# SCH_AC400-Controller_2024-06-21.net
KiCad netlist of a schematic drawn in EasyEDA
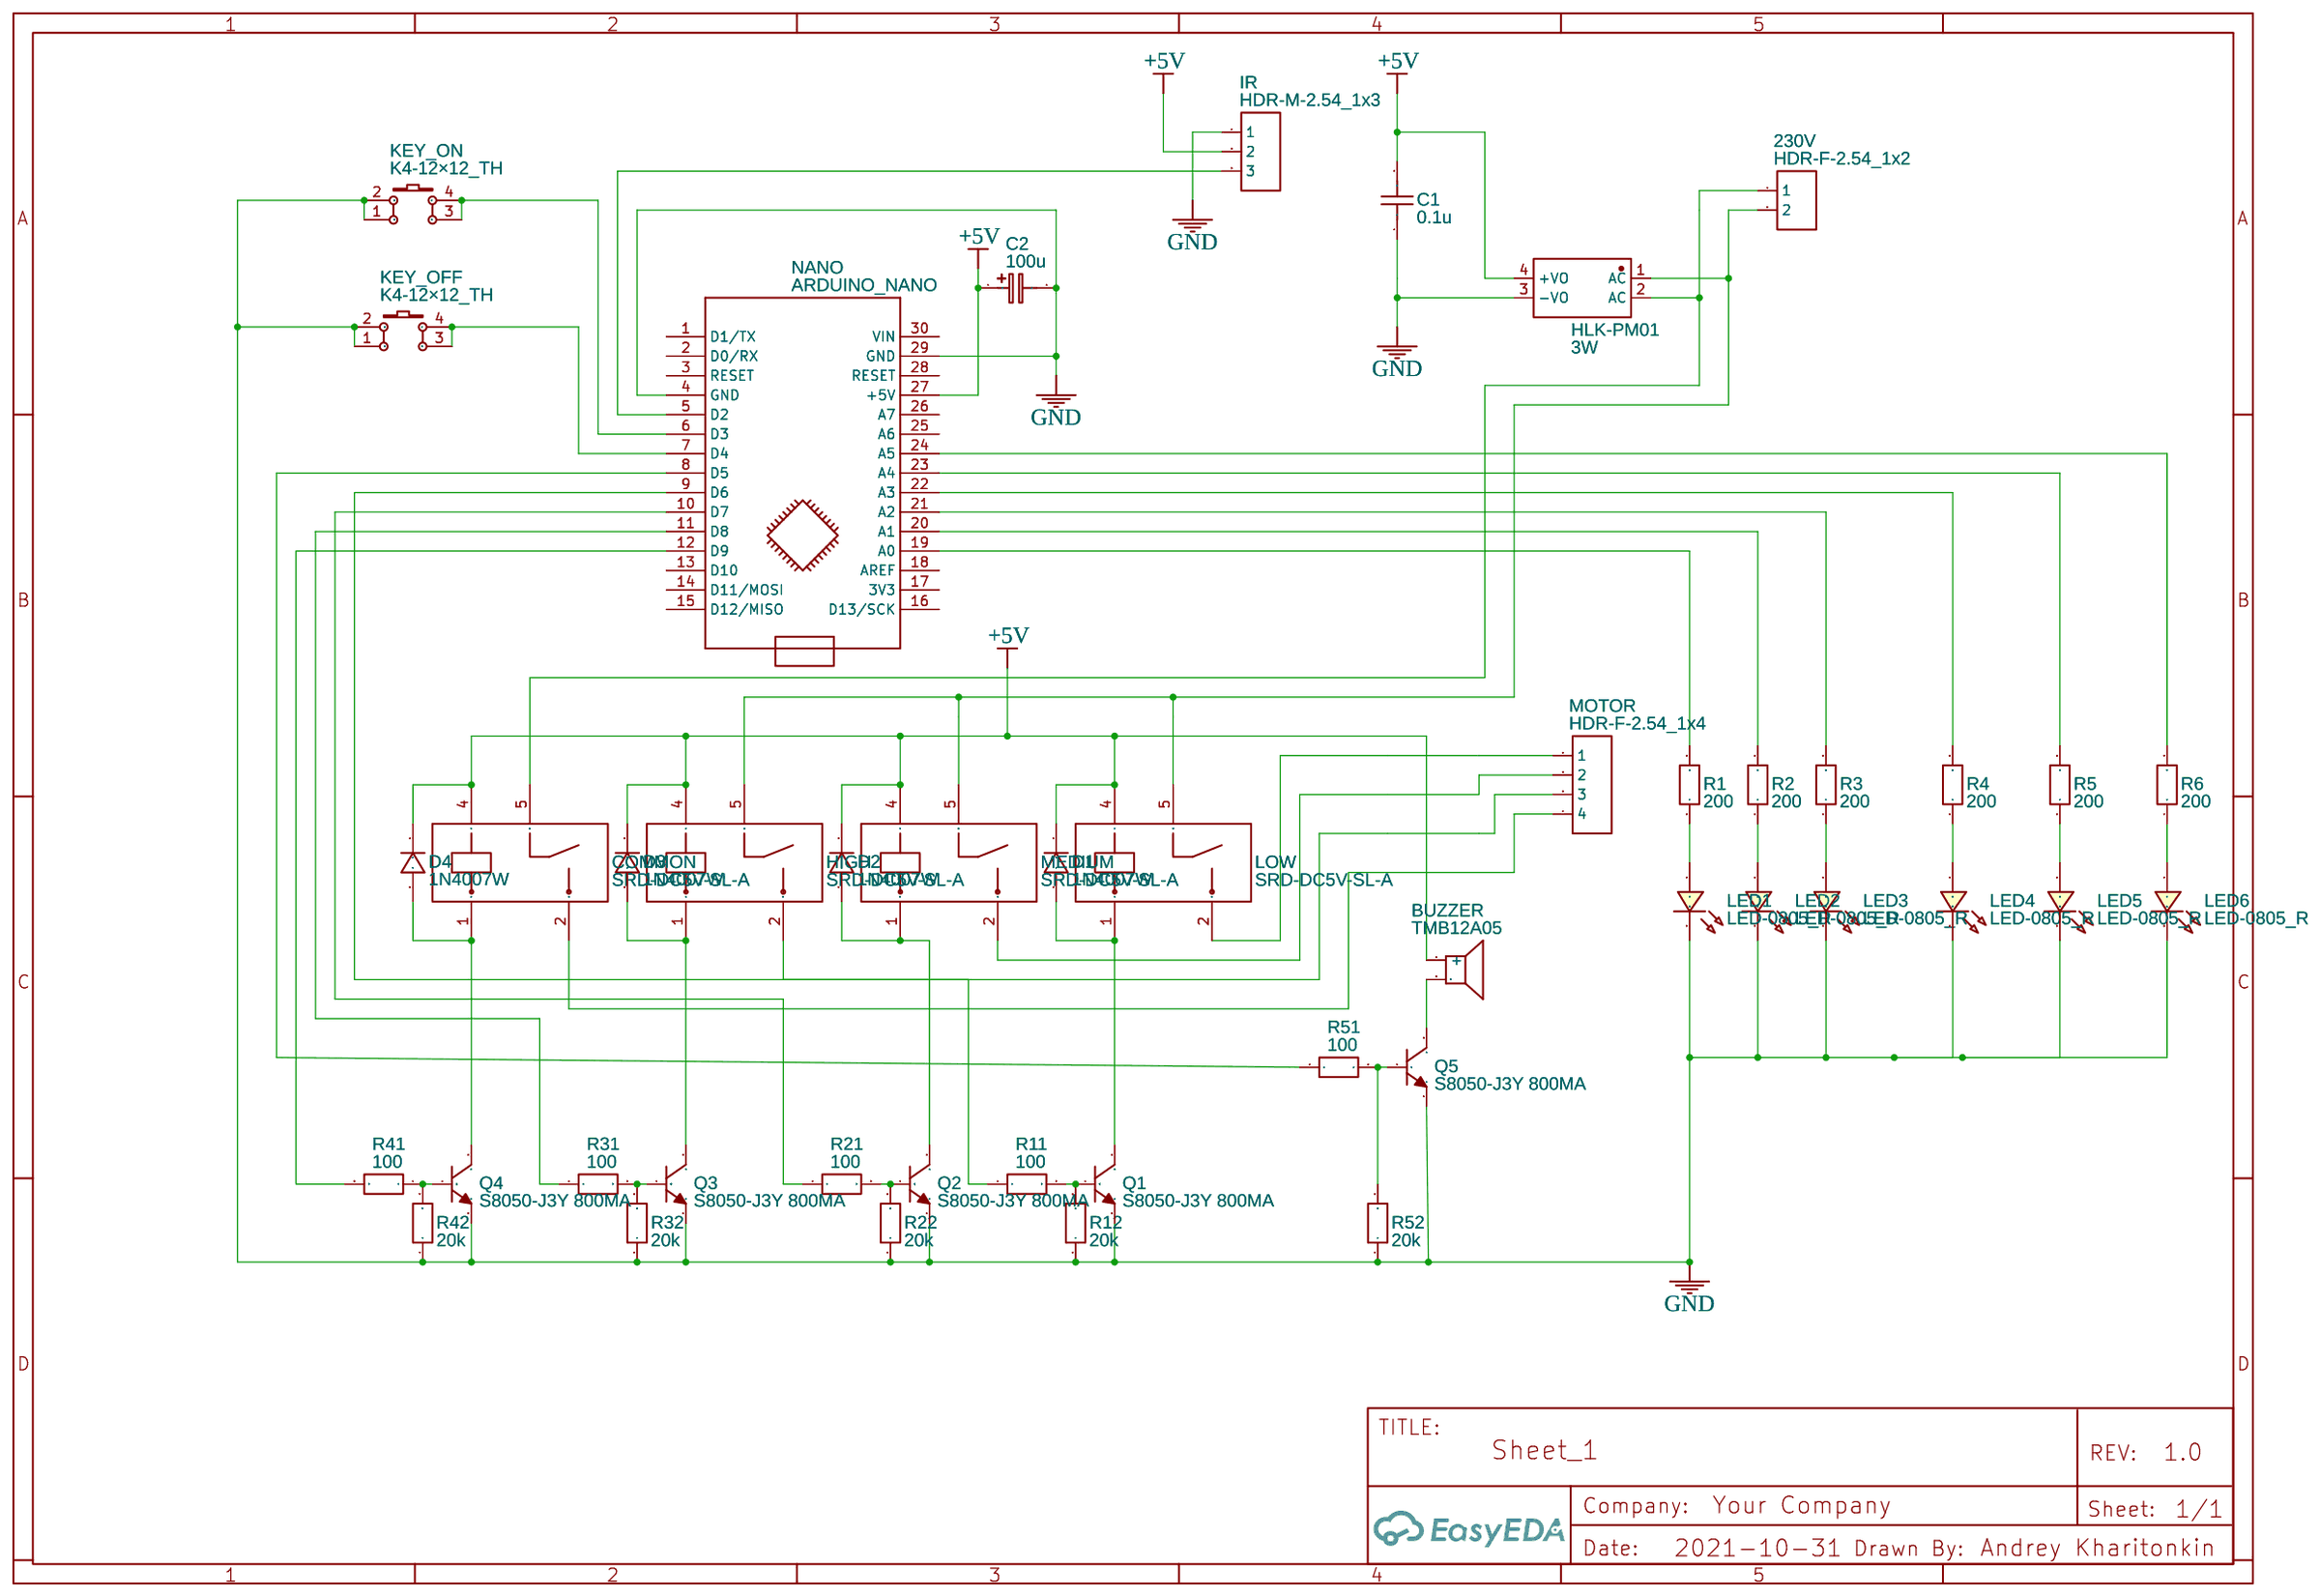
[diagram p0: schematic sheet]

(export (version "E")
  (design (tool "Eeschema 10.0.6"))
  (components
    (comp (ref "3W")
      (value "HLK-PM01")
      (fields (field (name "Manufacturer") "HI-LINK"))
      (libsource (lib "") (part "HLK-PM01"))
    )
    (comp (ref "230V") (value "HDR-F-2.54_1x2") (libsource (lib "") (part "HDR-F-2.54_1x2")))
    (comp (ref "BUZZER")
      (value "TMB12A05")
      (fields (field (name "Manufacturer") "HNDZ"))
      (libsource (lib "") (part "TMB12A05"))
    )
    (comp (ref "C1")
      (value "0.1u")
      (fields
        (field (name "Manufacturer Part") "CT41G-0805-2X1-50V-0.1uF-K(N)")
        (field (name "Manufacturer") "TORCH")
      )
      (libsource (lib "") (part "C_1206_US"))
    )
    (comp (ref "C2") (value "100u") (libsource (lib "") (part "CE_TH_D6.3×F2.5_EU")))
    (comp (ref "COMMON")
      (value "SRD-DC5V-SL-A")
      (fields (field (name "Manufacturer") "Ningbo Songle Relay"))
      (libsource (lib "") (part "SRD-DC5V-SL-A_2"))
    )
    (comp (ref "D1")
      (value "1N4007W")
      (fields (field (name "Manufacturer") "BLUE ROCKET"))
      (libsource (lib "") (part "1N4007W"))
    )
    (comp (ref "D2")
      (value "1N4007W")
      (fields (field (name "Manufacturer") "BLUE ROCKET"))
      (libsource (lib "") (part "1N4007W"))
    )
    (comp (ref "D3")
      (value "1N4007W")
      (fields (field (name "Manufacturer") "BLUE ROCKET"))
      (libsource (lib "") (part "1N4007W"))
    )
    (comp (ref "D4")
      (value "1N4007W")
      (fields (field (name "Manufacturer") "BLUE ROCKET"))
      (libsource (lib "") (part "1N4007W"))
    )
    (comp (ref "HIGH")
      (value "SRD-DC5V-SL-A")
      (fields (field (name "Manufacturer") "Ningbo Songle Relay"))
      (libsource (lib "") (part "SRD-DC5V-SL-A_1"))
    )
    (comp (ref "IR") (value "HDR-M-2.54_1x3") (libsource (lib "") (part "HDR-M-2.54_1x3")))
    (comp (ref "KEY_OFF")
      (value "K4-12×12_TH")
      (fields (field (name "Manufacturer Part") "K2-1103DP-M4SW-04") (field (name "Manufacturer") "韩国韩荣"))
      (libsource (lib "") (part "K4-12×12_TH_1"))
    )
    (comp (ref "KEY_ON")
      (value "K4-12×12_TH")
      (fields (field (name "Manufacturer Part") "K2-1103DP-M4SW-04") (field (name "Manufacturer") "韩国韩荣"))
      (libsource (lib "") (part "K4-12×12_TH"))
    )
    (comp (ref "LED1")
      (value "LED-0805_R")
      (fields
        (field (name "Manufacturer Part") "17-21SURC/S530-A3/TR8")
        (field (name "Manufacturer") "EVERLIGHT(台湾亿光)")
      )
      (libsource (lib "") (part "LED-0805_R"))
    )
    (comp (ref "LED2")
      (value "LED-0805_R")
      (fields
        (field (name "Manufacturer Part") "17-21SURC/S530-A3/TR8")
        (field (name "Manufacturer") "EVERLIGHT(台湾亿光)")
      )
      (libsource (lib "") (part "LED-0805_R"))
    )
    (comp (ref "LED3")
      (value "LED-0805_R")
      (fields
        (field (name "Manufacturer Part") "17-21SURC/S530-A3/TR8")
        (field (name "Manufacturer") "EVERLIGHT(台湾亿光)")
      )
      (libsource (lib "") (part "LED-0805_R"))
    )
    (comp (ref "LED4")
      (value "LED-0805_R")
      (fields
        (field (name "Manufacturer Part") "17-21SURC/S530-A3/TR8")
        (field (name "Manufacturer") "EVERLIGHT(台湾亿光)")
      )
      (libsource (lib "") (part "LED-0805_R"))
    )
    (comp (ref "LED5")
      (value "LED-0805_R")
      (fields
        (field (name "Manufacturer Part") "17-21SURC/S530-A3/TR8")
        (field (name "Manufacturer") "EVERLIGHT(台湾亿光)")
      )
      (libsource (lib "") (part "LED-0805_R"))
    )
    (comp (ref "LED6")
      (value "LED-0805_R")
      (fields
        (field (name "Manufacturer Part") "17-21SURC/S530-A3/TR8")
        (field (name "Manufacturer") "EVERLIGHT(台湾亿光)")
      )
      (libsource (lib "") (part "LED-0805_R"))
    )
    (comp (ref "LOW")
      (value "SRD-DC5V-SL-A")
      (fields (field (name "Manufacturer") "Ningbo Songle Relay"))
      (libsource (lib "") (part "SRD-DC5V-SL-A"))
    )
    (comp (ref "MEDIUM")
      (value "SRD-DC5V-SL-A")
      (fields (field (name "Manufacturer") "Ningbo Songle Relay"))
      (libsource (lib "") (part "SRD-DC5V-SL-A_3"))
    )
    (comp (ref "MOTOR") (value "HDR-F-2.54_1x4") (libsource (lib "") (part "HDR-F-2.54_1x4")))
    (comp (ref "NANO")
      (value "ARDUINO_NANO")
      (fields (field (name "Manufacturer Part") "?"))
      (libsource (lib "") (part "Unknown_405_-570"))
    )
    (comp (ref "Q1")
      (value "S8050-J3Y 800MA")
      (fields (field (name "Manufacturer") "IDCHIP(英锐芯)"))
      (libsource (lib "") (part "S8050-J3Y 800MA"))
    )
    (comp (ref "Q2")
      (value "S8050-J3Y 800MA")
      (fields (field (name "Manufacturer") "IDCHIP(英锐芯)"))
      (libsource (lib "") (part "S8050-J3Y 800MA"))
    )
    (comp (ref "Q3")
      (value "S8050-J3Y 800MA")
      (fields (field (name "Manufacturer") "IDCHIP(英锐芯)"))
      (libsource (lib "") (part "S8050-J3Y 800MA"))
    )
    (comp (ref "Q4")
      (value "S8050-J3Y 800MA")
      (fields (field (name "Manufacturer") "IDCHIP(英锐芯)"))
      (libsource (lib "") (part "S8050-J3Y 800MA"))
    )
    (comp (ref "Q5")
      (value "S8050-J3Y 800MA")
      (fields (field (name "Manufacturer") "IDCHIP(英锐芯)"))
      (libsource (lib "") (part "S8050-J3Y 800MA"))
    )
    (comp (ref "R1")
      (value "200")
      (fields (field (name "Manufacturer Part") "0805W8F2000T5E") (field (name "Manufacturer") "UniOhm"))
      (libsource (lib "") (part "R_0805_EU"))
    )
    (comp (ref "R2")
      (value "200")
      (fields (field (name "Manufacturer Part") "0805W8F2000T5E") (field (name "Manufacturer") "UniOhm"))
      (libsource (lib "") (part "R_0805_EU"))
    )
    (comp (ref "R3")
      (value "200")
      (fields (field (name "Manufacturer Part") "0805W8F2000T5E") (field (name "Manufacturer") "UniOhm"))
      (libsource (lib "") (part "R_0805_EU"))
    )
    (comp (ref "R4")
      (value "200")
      (fields (field (name "Manufacturer Part") "0805W8F2000T5E") (field (name "Manufacturer") "UniOhm"))
      (libsource (lib "") (part "R_0805_EU"))
    )
    (comp (ref "R5")
      (value "200")
      (fields (field (name "Manufacturer Part") "0805W8F2000T5E") (field (name "Manufacturer") "UniOhm"))
      (libsource (lib "") (part "R_0805_EU"))
    )
    (comp (ref "R6")
      (value "200")
      (fields (field (name "Manufacturer Part") "0805W8F2000T5E") (field (name "Manufacturer") "UniOhm"))
      (libsource (lib "") (part "R_0805_EU"))
    )
    (comp (ref "R11") (value "100") (libsource (lib "") (part "R_0805_EU_1")))
    (comp (ref "R12") (value "20k") (libsource (lib "") (part "R_0805_EU")))
    (comp (ref "R21") (value "100") (libsource (lib "") (part "R_0805_EU_1")))
    (comp (ref "R22") (value "20k") (libsource (lib "") (part "R_0805_EU")))
    (comp (ref "R31") (value "100") (libsource (lib "") (part "R_0805_EU_1")))
    (comp (ref "R32") (value "20k") (libsource (lib "") (part "R_0805_EU")))
    (comp (ref "R41") (value "100") (libsource (lib "") (part "R_0805_EU_2")))
    (comp (ref "R42") (value "20k") (libsource (lib "") (part "R_0805_EU")))
    (comp (ref "R51") (value "100") (libsource (lib "") (part "R_0805_EU_1")))
    (comp (ref "R52") (value "20k") (libsource (lib "") (part "R_0805_EU")))
  )
  (nets
    (net (code "1") (name "+5V") (class "Default")
      (node (ref "3W") (pin "4") (pinfunction "+VO_4") (pintype "unspecified"))
      (node (ref "BUZZER") (pin "1") (pinfunction "+_1") (pintype "unspecified"))
      (node (ref "C1") (pin "2") (pinfunction "2_2") (pintype "unspecified"))
      (node (ref "C2") (pin "1") (pinfunction "1_1") (pintype "unspecified"))
      (node (ref "COMMON") (pin "4") (pinfunction "4_4") (pintype "input"))
      (node (ref "D1") (pin "1") (pinfunction "1_1") (pintype "unspecified"))
      (node (ref "D2") (pin "1") (pinfunction "1_1") (pintype "unspecified"))
      (node (ref "D3") (pin "1") (pinfunction "1_1") (pintype "unspecified"))
      (node (ref "D4") (pin "1") (pinfunction "1_1") (pintype "unspecified"))
      (node (ref "HIGH") (pin "4") (pinfunction "4_4") (pintype "input"))
      (node (ref "IR") (pin "2") (pinfunction "2_2") (pintype "input"))
      (node (ref "LOW") (pin "4") (pinfunction "4_4") (pintype "input"))
      (node (ref "MEDIUM") (pin "4") (pinfunction "4_4") (pintype "input"))
      (node (ref "NANO") (pin "27") (pinfunction "+5V_27") (pintype "unspecified"))
    )
    (net (code "2") (name "GND") (class "Default")
      (node (ref "3W") (pin "3") (pinfunction "-VO_3") (pintype "unspecified"))
      (node (ref "C1") (pin "1") (pinfunction "1_1") (pintype "unspecified"))
      (node (ref "C2") (pin "2") (pinfunction "2_2") (pintype "unspecified"))
      (node (ref "IR") (pin "1") (pinfunction "1_1") (pintype "input"))
      (node (ref "KEY_OFF") (pin "1") (pinfunction "1_1") (pintype "unspecified"))
      (node (ref "KEY_OFF") (pin "2") (pinfunction "2_2") (pintype "unspecified"))
      (node (ref "KEY_ON") (pin "1") (pinfunction "1_1") (pintype "unspecified"))
      (node (ref "KEY_ON") (pin "2") (pinfunction "2_2") (pintype "unspecified"))
      (node (ref "LED1") (pin "2") (pinfunction "2_2") (pintype "unspecified"))
      (node (ref "LED2") (pin "2") (pinfunction "2_2") (pintype "unspecified"))
      (node (ref "LED3") (pin "2") (pinfunction "2_2") (pintype "unspecified"))
      (node (ref "LED4") (pin "2") (pinfunction "2_2") (pintype "unspecified"))
      (node (ref "LED5") (pin "2") (pinfunction "2_2") (pintype "unspecified"))
      (node (ref "LED6") (pin "2") (pinfunction "2_2") (pintype "unspecified"))
      (node (ref "NANO") (pin "29") (pinfunction "GND_29") (pintype "unspecified"))
      (node (ref "NANO") (pin "4") (pinfunction "GND_4") (pintype "unspecified"))
      (node (ref "Q1") (pin "2") (pinfunction "E_2") (pintype "input"))
      (node (ref "Q2") (pin "2") (pinfunction "E_2") (pintype "input"))
      (node (ref "Q3") (pin "2") (pinfunction "E_2") (pintype "input"))
      (node (ref "Q4") (pin "2") (pinfunction "E_2") (pintype "input"))
      (node (ref "Q5") (pin "2") (pinfunction "E_2") (pintype "input"))
      (node (ref "R12") (pin "1") (pinfunction "1_1") (pintype "unspecified"))
      (node (ref "R22") (pin "1") (pinfunction "1_1") (pintype "unspecified"))
      (node (ref "R32") (pin "1") (pinfunction "1_1") (pintype "unspecified"))
      (node (ref "R42") (pin "1") (pinfunction "1_1") (pintype "unspecified"))
      (node (ref "R52") (pin "1") (pinfunction "1_1") (pintype "unspecified"))
    )
    (net (code "3") (name "Net-(230V-Pad1)") (class "Default")
      (node (ref "230V") (pin "1") (pinfunction "1_1") (pintype "input"))
      (node (ref "3W") (pin "2") (pinfunction "AC_2") (pintype "unspecified"))
      (node (ref "COMMON") (pin "5") (pinfunction "5_5") (pintype "input"))
    )
    (net (code "4") (name "Net-(230V-Pad2)") (class "Default")
      (node (ref "230V") (pin "2") (pinfunction "2_2") (pintype "input"))
      (node (ref "3W") (pin "1") (pinfunction "AC_1") (pintype "unspecified"))
      (node (ref "HIGH") (pin "5") (pinfunction "5_5") (pintype "input"))
      (node (ref "LOW") (pin "5") (pinfunction "5_5") (pintype "input"))
      (node (ref "MEDIUM") (pin "5") (pinfunction "5_5") (pintype "input"))
    )
    (net (code "5") (name "Net-(COMMON-Pad2)") (class "Default")
      (node (ref "COMMON") (pin "2") (pinfunction "2_2") (pintype "input"))
      (node (ref "MOTOR") (pin "4") (pinfunction "4_4") (pintype "unspecified"))
    )
    (net (code "6") (name "Net-(HIGH-Pad2)") (class "Default")
      (node (ref "HIGH") (pin "2") (pinfunction "2_2") (pintype "input"))
      (node (ref "MOTOR") (pin "3") (pinfunction "3_3") (pintype "unspecified"))
    )
    (net (code "7") (name "Net-(LED1-Pad1)") (class "Default")
      (node (ref "LED1") (pin "1") (pinfunction "1_1") (pintype "unspecified"))
      (node (ref "R1") (pin "1") (pinfunction "1_1") (pintype "unspecified"))
    )
    (net (code "8") (name "Net-(LED2-Pad1)") (class "Default")
      (node (ref "LED2") (pin "1") (pinfunction "1_1") (pintype "unspecified"))
      (node (ref "R2") (pin "1") (pinfunction "1_1") (pintype "unspecified"))
    )
    (net (code "9") (name "Net-(LED3-Pad1)") (class "Default")
      (node (ref "LED3") (pin "1") (pinfunction "1_1") (pintype "unspecified"))
      (node (ref "R3") (pin "1") (pinfunction "1_1") (pintype "unspecified"))
    )
    (net (code "10") (name "Net-(LED4-Pad1)") (class "Default")
      (node (ref "LED4") (pin "1") (pinfunction "1_1") (pintype "unspecified"))
      (node (ref "R4") (pin "1") (pinfunction "1_1") (pintype "unspecified"))
    )
    (net (code "11") (name "Net-(LED5-Pad1)") (class "Default")
      (node (ref "LED5") (pin "1") (pinfunction "1_1") (pintype "unspecified"))
      (node (ref "R5") (pin "1") (pinfunction "1_1") (pintype "unspecified"))
    )
    (net (code "12") (name "Net-(LED6-Pad1)") (class "Default")
      (node (ref "LED6") (pin "1") (pinfunction "1_1") (pintype "unspecified"))
      (node (ref "R6") (pin "1") (pinfunction "1_1") (pintype "unspecified"))
    )
    (net (code "13") (name "Net-(LOW-Pad2)") (class "Default")
      (node (ref "LOW") (pin "2") (pinfunction "2_2") (pintype "input"))
      (node (ref "MOTOR") (pin "1") (pinfunction "1_1") (pintype "unspecified"))
    )
    (net (code "14") (name "Net-(MEDIUM-Pad2)") (class "Default")
      (node (ref "MEDIUM") (pin "2") (pinfunction "2_2") (pintype "input"))
      (node (ref "MOTOR") (pin "2") (pinfunction "2_2") (pintype "unspecified"))
    )
    (net (code "15") (name "Net-(NANO-A0)") (class "Default")
      (node (ref "NANO") (pin "19") (pinfunction "A0_19") (pintype "unspecified"))
      (node (ref "R1") (pin "2") (pinfunction "2_2") (pintype "unspecified"))
    )
    (net (code "16") (name "Net-(NANO-A1)") (class "Default")
      (node (ref "NANO") (pin "20") (pinfunction "A1_20") (pintype "unspecified"))
      (node (ref "R2") (pin "2") (pinfunction "2_2") (pintype "unspecified"))
    )
    (net (code "17") (name "Net-(NANO-A2)") (class "Default")
      (node (ref "NANO") (pin "21") (pinfunction "A2_21") (pintype "unspecified"))
      (node (ref "R3") (pin "2") (pinfunction "2_2") (pintype "unspecified"))
    )
    (net (code "18") (name "Net-(NANO-A3)") (class "Default")
      (node (ref "NANO") (pin "22") (pinfunction "A3_22") (pintype "unspecified"))
      (node (ref "R4") (pin "2") (pinfunction "2_2") (pintype "unspecified"))
    )
    (net (code "19") (name "Net-(NANO-A4)") (class "Default")
      (node (ref "NANO") (pin "23") (pinfunction "A4_23") (pintype "unspecified"))
      (node (ref "R5") (pin "2") (pinfunction "2_2") (pintype "unspecified"))
    )
    (net (code "20") (name "Net-(NANO-A5)") (class "Default")
      (node (ref "NANO") (pin "24") (pinfunction "A5_24") (pintype "unspecified"))
      (node (ref "R6") (pin "2") (pinfunction "2_2") (pintype "unspecified"))
    )
    (net (code "21") (name "Net-(NANO-D2)") (class "Default")
      (node (ref "IR") (pin "3") (pinfunction "3_3") (pintype "input"))
      (node (ref "NANO") (pin "5") (pinfunction "D2_5") (pintype "unspecified"))
    )
    (net (code "22") (name "Net-(NANO-D3)") (class "Default")
      (node (ref "KEY_ON") (pin "3") (pinfunction "3_3") (pintype "unspecified"))
      (node (ref "KEY_ON") (pin "4") (pinfunction "4_4") (pintype "unspecified"))
      (node (ref "NANO") (pin "6") (pinfunction "D3_6") (pintype "unspecified"))
    )
    (net (code "23") (name "Net-(NANO-D4)") (class "Default")
      (node (ref "KEY_OFF") (pin "3") (pinfunction "3_3") (pintype "unspecified"))
      (node (ref "KEY_OFF") (pin "4") (pinfunction "4_4") (pintype "unspecified"))
      (node (ref "NANO") (pin "7") (pinfunction "D4_7") (pintype "unspecified"))
    )
    (net (code "24") (name "Net-(NANO-D5)") (class "Default")
      (node (ref "NANO") (pin "8") (pinfunction "D5_8") (pintype "unspecified"))
      (node (ref "R51") (pin "1") (pinfunction "1_1") (pintype "unspecified"))
    )
    (net (code "25") (name "Net-(NANO-D6)") (class "Default")
      (node (ref "NANO") (pin "9") (pinfunction "D6_9") (pintype "unspecified"))
      (node (ref "R11") (pin "1") (pinfunction "1_1") (pintype "unspecified"))
    )
    (net (code "26") (name "Net-(NANO-D7)") (class "Default")
      (node (ref "NANO") (pin "10") (pinfunction "D7_10") (pintype "unspecified"))
      (node (ref "R21") (pin "1") (pinfunction "1_1") (pintype "unspecified"))
    )
    (net (code "27") (name "Net-(NANO-D8)") (class "Default")
      (node (ref "NANO") (pin "11") (pinfunction "D8_11") (pintype "unspecified"))
      (node (ref "R31") (pin "1") (pinfunction "1_1") (pintype "unspecified"))
    )
    (net (code "28") (name "Net-(NANO-D9)") (class "Default")
      (node (ref "NANO") (pin "12") (pinfunction "D9_12") (pintype "unspecified"))
      (node (ref "R41") (pin "2") (pinfunction "2_2") (pintype "unspecified"))
    )
    (net (code "29") (name "Net-(Q1-B)") (class "Default")
      (node (ref "Q1") (pin "1") (pinfunction "B_1") (pintype "input"))
      (node (ref "R11") (pin "2") (pinfunction "2_2") (pintype "unspecified"))
      (node (ref "R12") (pin "2") (pinfunction "2_2") (pintype "unspecified"))
    )
    (net (code "30") (name "Net-(Q1-C)") (class "Default")
      (node (ref "D1") (pin "2") (pinfunction "2_2") (pintype "unspecified"))
      (node (ref "LOW") (pin "1") (pinfunction "1_1") (pintype "input"))
      (node (ref "Q1") (pin "3") (pinfunction "C_3") (pintype "input"))
    )
    (net (code "31") (name "Net-(Q2-B)") (class "Default")
      (node (ref "Q2") (pin "1") (pinfunction "B_1") (pintype "input"))
      (node (ref "R21") (pin "2") (pinfunction "2_2") (pintype "unspecified"))
      (node (ref "R22") (pin "2") (pinfunction "2_2") (pintype "unspecified"))
    )
    (net (code "32") (name "Net-(Q2-C)") (class "Default")
      (node (ref "D2") (pin "2") (pinfunction "2_2") (pintype "unspecified"))
      (node (ref "MEDIUM") (pin "1") (pinfunction "1_1") (pintype "input"))
      (node (ref "Q2") (pin "3") (pinfunction "C_3") (pintype "input"))
    )
    (net (code "33") (name "Net-(Q3-B)") (class "Default")
      (node (ref "Q3") (pin "1") (pinfunction "B_1") (pintype "input"))
      (node (ref "R31") (pin "2") (pinfunction "2_2") (pintype "unspecified"))
      (node (ref "R32") (pin "2") (pinfunction "2_2") (pintype "unspecified"))
    )
    (net (code "34") (name "Net-(Q3-C)") (class "Default")
      (node (ref "D3") (pin "2") (pinfunction "2_2") (pintype "unspecified"))
      (node (ref "HIGH") (pin "1") (pinfunction "1_1") (pintype "input"))
      (node (ref "Q3") (pin "3") (pinfunction "C_3") (pintype "input"))
    )
    (net (code "35") (name "Net-(Q4-B)") (class "Default")
      (node (ref "Q4") (pin "1") (pinfunction "B_1") (pintype "input"))
      (node (ref "R41") (pin "1") (pinfunction "1_1") (pintype "unspecified"))
      (node (ref "R42") (pin "2") (pinfunction "2_2") (pintype "unspecified"))
    )
    (net (code "36") (name "Net-(Q4-C)") (class "Default")
      (node (ref "COMMON") (pin "1") (pinfunction "1_1") (pintype "input"))
      (node (ref "D4") (pin "2") (pinfunction "2_2") (pintype "unspecified"))
      (node (ref "Q4") (pin "3") (pinfunction "C_3") (pintype "input"))
    )
    (net (code "37") (name "Net-(Q5-B)") (class "Default")
      (node (ref "Q5") (pin "1") (pinfunction "B_1") (pintype "input"))
      (node (ref "R51") (pin "2") (pinfunction "2_2") (pintype "unspecified"))
      (node (ref "R52") (pin "2") (pinfunction "2_2") (pintype "unspecified"))
    )
    (net (code "38") (name "Net-(Q5-C)") (class "Default")
      (node (ref "BUZZER") (pin "2") (pinfunction "2_2") (pintype "unspecified"))
      (node (ref "Q5") (pin "3") (pinfunction "C_3") (pintype "input"))
    )
    (net (code "39") (name "unconnected-(NANO-3V3-Pad17)") (class "Default")
      (node (ref "NANO") (pin "17") (pinfunction "3V3_17") (pintype "unspecified"))
    )
    (net (code "40") (name "unconnected-(NANO-A6-Pad25)") (class "Default")
      (node (ref "NANO") (pin "25") (pinfunction "A6_25") (pintype "unspecified"))
    )
    (net (code "41") (name "unconnected-(NANO-A7-Pad26)") (class "Default")
      (node (ref "NANO") (pin "26") (pinfunction "A7_26") (pintype "unspecified"))
    )
    (net (code "42") (name "unconnected-(NANO-AREF-Pad18)") (class "Default")
      (node (ref "NANO") (pin "18") (pinfunction "AREF_18") (pintype "unspecified"))
    )
    (net (code "43") (name "unconnected-(NANO-D0{slash}RX-Pad2)") (class "Default")
      (node (ref "NANO") (pin "2") (pinfunction "D0/RX_2") (pintype "unspecified"))
    )
    (net (code "44") (name "unconnected-(NANO-D1{slash}TX-Pad1)") (class "Default")
      (node (ref "NANO") (pin "1") (pinfunction "D1/TX_1") (pintype "unspecified"))
    )
    (net (code "45") (name "unconnected-(NANO-D10-Pad13)") (class "Default")
      (node (ref "NANO") (pin "13") (pinfunction "D10_13") (pintype "unspecified"))
    )
    (net (code "46") (name "unconnected-(NANO-D11{slash}MOSI-Pad14)") (class "Default")
      (node (ref "NANO") (pin "14") (pinfunction "D11/MOSI_14") (pintype "unspecified"))
    )
    (net (code "47") (name "unconnected-(NANO-D12{slash}MISO-Pad15)") (class "Default")
      (node (ref "NANO") (pin "15") (pinfunction "D12/MISO_15") (pintype "unspecified"))
    )
    (net (code "48") (name "unconnected-(NANO-D13{slash}SCK-Pad16)") (class "Default")
      (node (ref "NANO") (pin "16") (pinfunction "D13/SCK_16") (pintype "unspecified"))
    )
    (net (code "49") (name "unconnected-(NANO-RESET-Pad3)") (class "Default")
      (node (ref "NANO") (pin "3") (pinfunction "RESET_3") (pintype "unspecified"))
    )
    (net (code "50") (name "unconnected-(NANO-RESET-Pad28)") (class "Default")
      (node (ref "NANO") (pin "28") (pinfunction "RESET_28") (pintype "unspecified"))
    )
    (net (code "51") (name "unconnected-(NANO-VIN-Pad30)") (class "Default")
      (node (ref "NANO") (pin "30") (pinfunction "VIN_30") (pintype "unspecified"))
    )
  )
)
